# EEZ_DIB_module_template_isolated.net
KiCad netlist of a schematic drawn in EAGLE
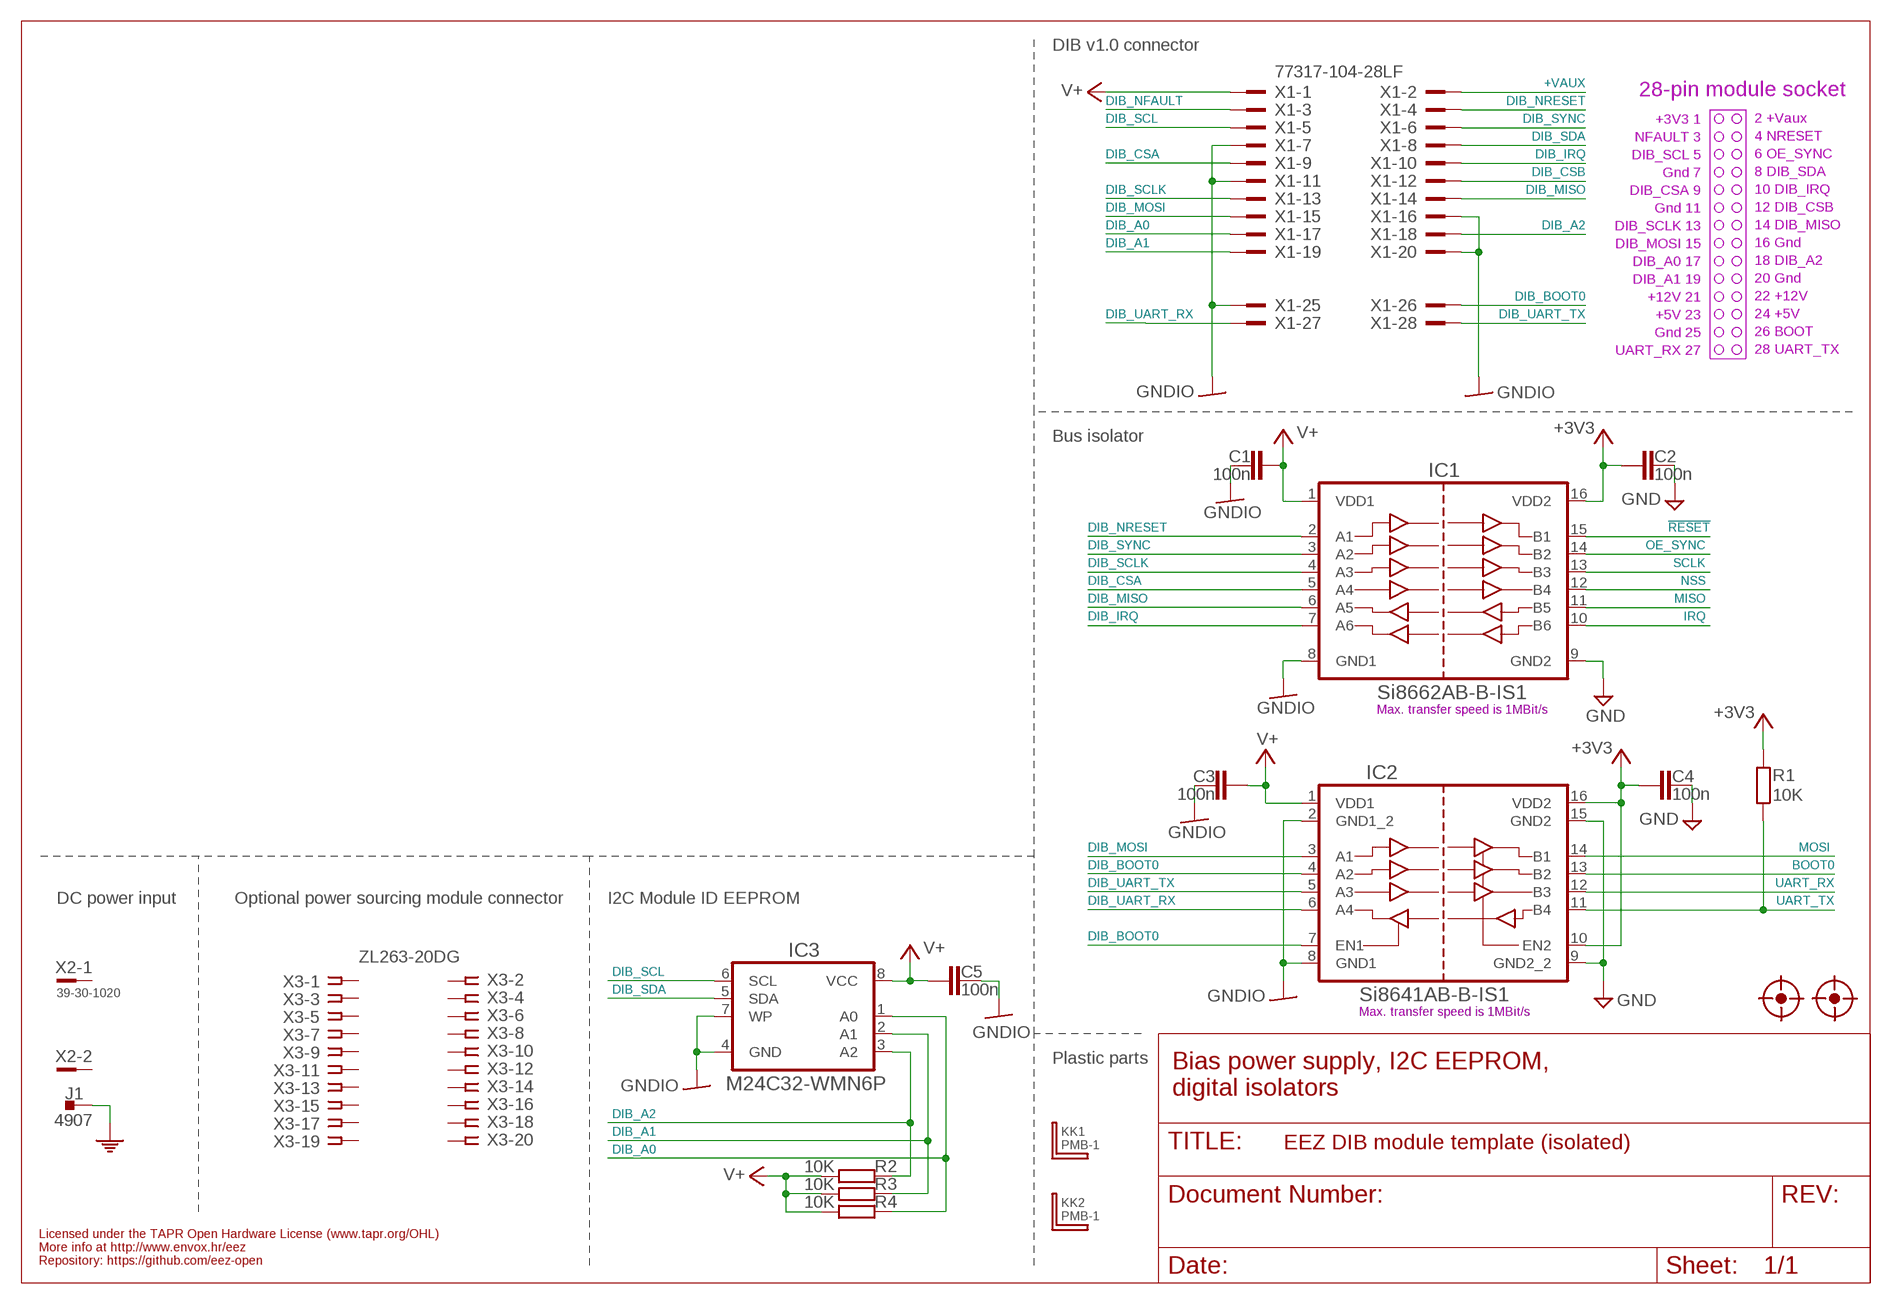
[diagram p0: schematic, sheet 1]

(export (version "E")
  (design (tool "Eeschema 10.0.6"))
  (components
    (comp (ref "C1")
      (value "100n")
      (footprint "eagle-import:C0603")
      (libsource (lib "eagle-import") (part "C-EUC0603"))
    )
    (comp (ref "C2")
      (value "100n")
      (footprint "eagle-import:C0603")
      (libsource (lib "eagle-import") (part "C-EUC0603"))
    )
    (comp (ref "C3")
      (value "100n")
      (footprint "eagle-import:C0603")
      (libsource (lib "eagle-import") (part "C-EUC0603"))
    )
    (comp (ref "C4")
      (value "100n")
      (footprint "eagle-import:C0603")
      (libsource (lib "eagle-import") (part "C-EUC0603"))
    )
    (comp (ref "C5")
      (value "100n")
      (footprint "eagle-import:C0603")
      (libsource (lib "eagle-import") (part "C-EUC0603"))
    )
    (comp (ref "FM1")
      (value "FIDUCIAL_2")
      (footprint "eagle-import:FIDUCIAL_DUAL")
      (libsource (lib "eagle-import") (part "FIDUCIAL_2"))
    )
    (comp (ref "FM2")
      (value "FIDUCIAL_2")
      (footprint "eagle-import:FIDUCIAL_DUAL")
      (libsource (lib "eagle-import") (part "FIDUCIAL_2"))
    )
    (comp (ref "IC1")
      (value "Si8662AB-B-IS1")
      (footprint "eagle-import:SOIC-16")
      (libsource (lib "eagle-import") (part "SI8662NSOIC-16"))
    )
    (comp (ref "IC2")
      (value "Si8641AB-B-IS1")
      (footprint "eagle-import:SOIC-16")
      (libsource (lib "eagle-import") (part "SI8641NSOIC-16"))
    )
    (comp (ref "IC3")
      (value "M24C32-WMN6P")
      (footprint "eagle-import:SOIC127P600X173-8N")
      (libsource (lib "eagle-import") (part "AT24CXXSOIC8"))
    )
    (comp (ref "J1")
      (value "4907")
      (footprint "eagle-import:PCB_TAB-4907")
      (libsource (lib "eagle-import") (part "PCB_TAB-4907"))
    )
    (comp (ref "KK1")
      (value "PMB-1")
      (footprint "eagle-import:PCB-MB")
      (libsource (lib "eagle-import") (part "PCB-MB"))
    )
    (comp (ref "KK2")
      (value "PMB-1")
      (footprint "eagle-import:PCB-MB")
      (libsource (lib "eagle-import") (part "PCB-MB"))
    )
    (comp (ref "R1")
      (value "10K")
      (footprint "eagle-import:R0805")
      (libsource (lib "eagle-import") (part "R-EU_R0805"))
    )
    (comp (ref "R2")
      (value "10K")
      (footprint "eagle-import:R0805")
      (libsource (lib "eagle-import") (part "R-EU_R0805"))
    )
    (comp (ref "R3")
      (value "10K")
      (footprint "eagle-import:R0805")
      (libsource (lib "eagle-import") (part "R-EU_R0805"))
    )
    (comp (ref "R4")
      (value "10K")
      (footprint "eagle-import:R0805")
      (libsource (lib "eagle-import") (part "R-EU_R0805"))
    )
    (comp (ref "X1")
      (value "77317-104-28LF")
      (footprint "eagle-import:77317-104-28LF")
      (libsource (lib "eagle-import") (part "77317-104-28LF"))
    )
    (comp (ref "X2")
      (value "39-30-1020")
      (footprint "eagle-import:MINIFIT_39301020")
      (libsource (lib "eagle-import") (part "MINIFIT_39301020"))
    )
    (comp (ref "X3")
      (value "ZL263-20DG")
      (footprint "eagle-import:SSW-110-02-T-D-RA")
      (libsource (lib "eagle-import") (part "SSW-110-02-T-D-RA"))
    )
  )
  (nets
    (net (code "1") (name "+3V3") (class "Default")
      (node (ref "C2") (pin "2") (pinfunction "2_2") (pintype "passive"))
      (node (ref "C4") (pin "2") (pinfunction "2_2") (pintype "passive"))
      (node (ref "IC1") (pin "16") (pinfunction "VDD2_16") (pintype "passive"))
      (node (ref "IC2") (pin "10") (pinfunction "EN2_10") (pintype "input"))
      (node (ref "IC2") (pin "16") (pinfunction "VDD2_16") (pintype "passive"))
      (node (ref "R1") (pin "2") (pinfunction "2_2") (pintype "passive"))
    )
    (net (code "2") (name "/+VAUX") (class "Default")
      (node (ref "X1") (pin "2") (pinfunction "1_2") (pintype "passive"))
    )
    (net (code "3") (name "/BOOT0") (class "Default")
      (node (ref "IC2") (pin "13") (pinfunction "B2_13") (pintype "output"))
    )
    (net (code "4") (name "/DIB_A0") (class "Default")
      (node (ref "IC3") (pin "1") (pinfunction "A0_1") (pintype "input"))
      (node (ref "R4") (pin "2") (pinfunction "2_2") (pintype "passive"))
      (node (ref "X1") (pin "17") (pinfunction "1_17") (pintype "passive"))
    )
    (net (code "5") (name "/DIB_A1") (class "Default")
      (node (ref "IC3") (pin "2") (pinfunction "A1_2") (pintype "input"))
      (node (ref "R3") (pin "2") (pinfunction "2_2") (pintype "passive"))
      (node (ref "X1") (pin "19") (pinfunction "1_19") (pintype "passive"))
    )
    (net (code "6") (name "/DIB_A2") (class "Default")
      (node (ref "IC3") (pin "3") (pinfunction "A2_3") (pintype "input"))
      (node (ref "R2") (pin "2") (pinfunction "2_2") (pintype "passive"))
      (node (ref "X1") (pin "18") (pinfunction "1_18") (pintype "passive"))
    )
    (net (code "7") (name "/DIB_BOOT0") (class "Default")
      (node (ref "IC2") (pin "4") (pinfunction "A2_4") (pintype "input"))
      (node (ref "IC2") (pin "7") (pinfunction "EN1_7") (pintype "input"))
      (node (ref "X1") (pin "26") (pinfunction "1_26") (pintype "passive"))
    )
    (net (code "8") (name "/DIB_CSA") (class "Default")
      (node (ref "IC1") (pin "5") (pinfunction "A4_5") (pintype "input"))
      (node (ref "X1") (pin "9") (pinfunction "1_9") (pintype "passive"))
    )
    (net (code "9") (name "/DIB_CSB") (class "Default")
      (node (ref "X1") (pin "12") (pinfunction "1_12") (pintype "passive"))
    )
    (net (code "10") (name "/DIB_IRQ") (class "Default")
      (node (ref "IC1") (pin "7") (pinfunction "A6_7") (pintype "output"))
      (node (ref "X1") (pin "10") (pinfunction "1_10") (pintype "passive"))
    )
    (net (code "11") (name "/DIB_MISO") (class "Default")
      (node (ref "IC1") (pin "6") (pinfunction "A5_6") (pintype "output"))
      (node (ref "X1") (pin "14") (pinfunction "1_14") (pintype "passive"))
    )
    (net (code "12") (name "/DIB_MOSI") (class "Default")
      (node (ref "IC2") (pin "3") (pinfunction "A1_3") (pintype "input"))
      (node (ref "X1") (pin "15") (pinfunction "1_15") (pintype "passive"))
    )
    (net (code "13") (name "/DIB_NFAULT") (class "Default")
      (node (ref "X1") (pin "3") (pinfunction "1_3") (pintype "passive"))
    )
    (net (code "14") (name "/DIB_NRESET") (class "Default")
      (node (ref "IC1") (pin "2") (pinfunction "A1_2") (pintype "input"))
      (node (ref "X1") (pin "4") (pinfunction "1_4") (pintype "passive"))
    )
    (net (code "15") (name "/DIB_SCL") (class "Default")
      (node (ref "IC3") (pin "6") (pinfunction "SCL_6") (pintype "bidirectional"))
      (node (ref "X1") (pin "5") (pinfunction "1_5") (pintype "passive"))
    )
    (net (code "16") (name "/DIB_SCLK") (class "Default")
      (node (ref "IC1") (pin "4") (pinfunction "A3_4") (pintype "input"))
      (node (ref "X1") (pin "13") (pinfunction "1_13") (pintype "passive"))
    )
    (net (code "17") (name "/DIB_SDA") (class "Default")
      (node (ref "IC3") (pin "5") (pinfunction "SDA_5") (pintype "bidirectional"))
      (node (ref "X1") (pin "8") (pinfunction "1_8") (pintype "passive"))
    )
    (net (code "18") (name "/DIB_SYNC") (class "Default")
      (node (ref "IC1") (pin "3") (pinfunction "A2_3") (pintype "input"))
      (node (ref "X1") (pin "6") (pinfunction "1_6") (pintype "passive"))
    )
    (net (code "19") (name "/DIB_UART_RX") (class "Default")
      (node (ref "IC2") (pin "6") (pinfunction "A4_6") (pintype "output"))
      (node (ref "X1") (pin "27") (pinfunction "1_27") (pintype "passive"))
    )
    (net (code "20") (name "/DIB_UART_TX") (class "Default")
      (node (ref "IC2") (pin "5") (pinfunction "A3_5") (pintype "input"))
      (node (ref "X1") (pin "28") (pinfunction "1_28") (pintype "passive"))
    )
    (net (code "21") (name "/IRQ") (class "Default")
      (node (ref "IC1") (pin "10") (pinfunction "B6_10") (pintype "input"))
    )
    (net (code "22") (name "/MISO") (class "Default")
      (node (ref "IC1") (pin "11") (pinfunction "B5_11") (pintype "input"))
    )
    (net (code "23") (name "/MOSI") (class "Default")
      (node (ref "IC2") (pin "14") (pinfunction "B1_14") (pintype "output"))
    )
    (net (code "24") (name "/NSS") (class "Default")
      (node (ref "IC1") (pin "12") (pinfunction "B4_12") (pintype "output"))
    )
    (net (code "25") (name "/OE_SYNC") (class "Default")
      (node (ref "IC1") (pin "14") (pinfunction "B2_14") (pintype "output"))
    )
    (net (code "26") (name "/SCLK") (class "Default")
      (node (ref "IC1") (pin "13") (pinfunction "B3_13") (pintype "output"))
    )
    (net (code "27") (name "/UART_RX") (class "Default")
      (node (ref "IC2") (pin "12") (pinfunction "B3_12") (pintype "output"))
    )
    (net (code "28") (name "/UART_TX") (class "Default")
      (node (ref "IC2") (pin "11") (pinfunction "B4_11") (pintype "input"))
      (node (ref "R1") (pin "1") (pinfunction "1_1") (pintype "passive"))
    )
    (net (code "29") (name "/~{RESET}") (class "Default")
      (node (ref "IC1") (pin "15") (pinfunction "B1_15") (pintype "output"))
    )
    (net (code "30") (name "GND") (class "Default")
      (node (ref "C2") (pin "1") (pinfunction "1_1") (pintype "passive"))
      (node (ref "C4") (pin "1") (pinfunction "1_1") (pintype "passive"))
      (node (ref "IC1") (pin "9") (pinfunction "GND2_9") (pintype "passive"))
      (node (ref "IC2") (pin "15") (pinfunction "GND2_15") (pintype "passive"))
      (node (ref "IC2") (pin "9") (pinfunction "GND2_2_9") (pintype "passive"))
    )
    (net (code "31") (name "GNDIO") (class "Default")
      (node (ref "C1") (pin "2") (pinfunction "2_2") (pintype "passive"))
      (node (ref "C3") (pin "2") (pinfunction "2_2") (pintype "passive"))
      (node (ref "C5") (pin "1") (pinfunction "1_1") (pintype "passive"))
      (node (ref "IC1") (pin "8") (pinfunction "GND1_8") (pintype "passive"))
      (node (ref "IC2") (pin "2") (pinfunction "GND1_2_2") (pintype "passive"))
      (node (ref "IC2") (pin "8") (pinfunction "GND1_8") (pintype "passive"))
      (node (ref "IC3") (pin "4") (pinfunction "GND_4") (pintype "passive"))
      (node (ref "IC3") (pin "7") (pinfunction "WP_7") (pintype "input"))
      (node (ref "X1") (pin "11") (pinfunction "1_11") (pintype "passive"))
      (node (ref "X1") (pin "16") (pinfunction "1_16") (pintype "passive"))
      (node (ref "X1") (pin "20") (pinfunction "1_20") (pintype "passive"))
      (node (ref "X1") (pin "25") (pinfunction "1_25") (pintype "passive"))
      (node (ref "X1") (pin "7") (pinfunction "1_7") (pintype "passive"))
    )
    (net (code "32") (name "PE") (class "Default")
      (node (ref "J1") (pin "1") (pinfunction "P$1_1") (pintype "bidirectional"))
      (node (ref "J1") (pin "2") (pinfunction "P$1_2") (pintype "bidirectional"))
    )
    (net (code "33") (name "V+") (class "Default")
      (node (ref "C1") (pin "1") (pinfunction "1_1") (pintype "passive"))
      (node (ref "C3") (pin "1") (pinfunction "1_1") (pintype "passive"))
      (node (ref "C5") (pin "2") (pinfunction "2_2") (pintype "passive"))
      (node (ref "IC1") (pin "1") (pinfunction "VDD1_1") (pintype "passive"))
      (node (ref "IC2") (pin "1") (pinfunction "VDD1_1") (pintype "passive"))
      (node (ref "IC3") (pin "8") (pinfunction "VCC_8") (pintype "power_in"))
      (node (ref "R2") (pin "1") (pinfunction "1_1") (pintype "passive"))
      (node (ref "R3") (pin "1") (pinfunction "1_1") (pintype "passive"))
      (node (ref "R4") (pin "1") (pinfunction "1_1") (pintype "passive"))
      (node (ref "X1") (pin "1") (pinfunction "1_1") (pintype "passive"))
    )
    (net (code "34") (name "unconnected-(X2-Pad1)") (class "Default")
      (node (ref "X2") (pin "1") (pinfunction "1_1") (pintype "passive"))
    )
    (net (code "35") (name "unconnected-(X2B-1-Pad2)") (class "Default")
      (node (ref "X2") (pin "2") (pinfunction "1_2") (pintype "passive"))
    )
    (net (code "36") (name "unconnected-(X3-Pad1)") (class "Default")
      (node (ref "X3") (pin "1") (pinfunction "1_1") (pintype "passive"))
    )
    (net (code "37") (name "unconnected-(X3B-1-Pad10)") (class "Default")
      (node (ref "X3") (pin "10") (pinfunction "1_10") (pintype "passive"))
    )
    (net (code "38") (name "unconnected-(X3C-1-Pad11)") (class "Default")
      (node (ref "X3") (pin "11") (pinfunction "1_11") (pintype "passive"))
    )
    (net (code "39") (name "unconnected-(X3D-1-Pad12)") (class "Default")
      (node (ref "X3") (pin "12") (pinfunction "1_12") (pintype "passive"))
    )
    (net (code "40") (name "unconnected-(X3E-1-Pad13)") (class "Default")
      (node (ref "X3") (pin "13") (pinfunction "1_13") (pintype "passive"))
    )
    (net (code "41") (name "unconnected-(X3F-1-Pad14)") (class "Default")
      (node (ref "X3") (pin "14") (pinfunction "1_14") (pintype "passive"))
    )
    (net (code "42") (name "unconnected-(X3G-1-Pad15)") (class "Default")
      (node (ref "X3") (pin "15") (pinfunction "1_15") (pintype "passive"))
    )
    (net (code "43") (name "unconnected-(X3H-1-Pad16)") (class "Default")
      (node (ref "X3") (pin "16") (pinfunction "1_16") (pintype "passive"))
    )
    (net (code "44") (name "unconnected-(X3I-1-Pad17)") (class "Default")
      (node (ref "X3") (pin "17") (pinfunction "1_17") (pintype "passive"))
    )
    (net (code "45") (name "unconnected-(X3J-1-Pad18)") (class "Default")
      (node (ref "X3") (pin "18") (pinfunction "1_18") (pintype "passive"))
    )
    (net (code "46") (name "unconnected-(X3K-1-Pad19)") (class "Default")
      (node (ref "X3") (pin "19") (pinfunction "1_19") (pintype "passive"))
    )
    (net (code "47") (name "unconnected-(X3L-1-Pad2)") (class "Default")
      (node (ref "X3") (pin "2") (pinfunction "1_2") (pintype "passive"))
    )
    (net (code "48") (name "unconnected-(X3M-1-Pad20)") (class "Default")
      (node (ref "X3") (pin "20") (pinfunction "1_20") (pintype "passive"))
    )
    (net (code "49") (name "unconnected-(X3N-1-Pad3)") (class "Default")
      (node (ref "X3") (pin "3") (pinfunction "1_3") (pintype "passive"))
    )
    (net (code "50") (name "unconnected-(X3O-1-Pad4)") (class "Default")
      (node (ref "X3") (pin "4") (pinfunction "1_4") (pintype "passive"))
    )
    (net (code "51") (name "unconnected-(X3P-1-Pad5)") (class "Default")
      (node (ref "X3") (pin "5") (pinfunction "1_5") (pintype "passive"))
    )
    (net (code "52") (name "unconnected-(X3Q-1-Pad6)") (class "Default")
      (node (ref "X3") (pin "6") (pinfunction "1_6") (pintype "passive"))
    )
    (net (code "53") (name "unconnected-(X3R-1-Pad7)") (class "Default")
      (node (ref "X3") (pin "7") (pinfunction "1_7") (pintype "passive"))
    )
    (net (code "54") (name "unconnected-(X3S-1-Pad8)") (class "Default")
      (node (ref "X3") (pin "8") (pinfunction "1_8") (pintype "passive"))
    )
    (net (code "55") (name "unconnected-(X3T-1-Pad9)") (class "Default")
      (node (ref "X3") (pin "9") (pinfunction "1_9") (pintype "passive"))
    )
  )
)
